# Sheet2.net
KiCad netlist of a schematic drawn in Altium Designer
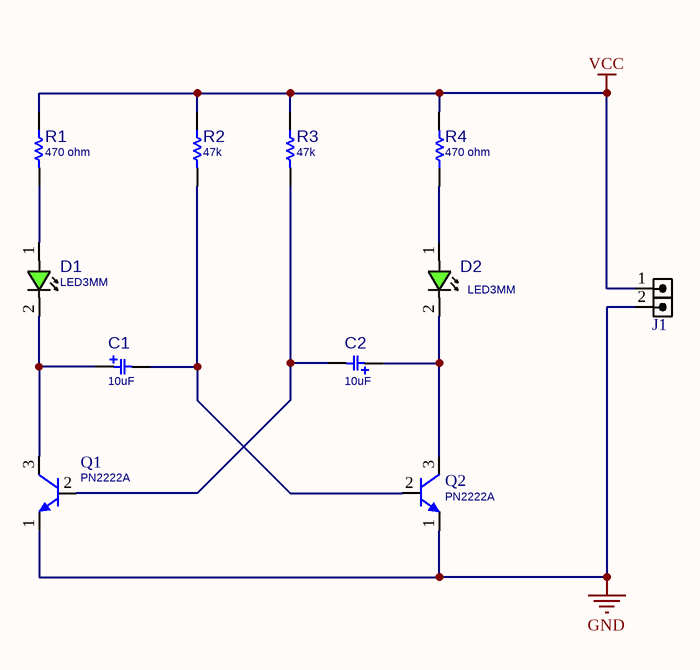
[diagram p0: Sheet2.SchDoc]

(export (version "E")
  (design (tool "Eeschema 10.0.6"))
  (components
    (comp (ref "C1")
      (value "10uF")
      (footprint "C_EL_8X14")
      (description "CAP, THD, ELEC,")
      (fields (field (name "MANF_P#") "MANF_PART#") (field (name "MANF") "MANF"))
      (libsource (lib "passive_thd") (part "CAP_THD_EL"))
    )
    (comp (ref "C2")
      (value "10uF")
      (footprint "C_EL_8X14")
      (description "CAP, THD, ELEC,")
      (fields (field (name "MANF_P#") "MANF_PART#") (field (name "MANF") "MANF"))
      (libsource (lib "passive_thd") (part "CAP_THD_EL"))
    )
    (comp (ref "D1")
      (value "LED3MM")
      (footprint "LED3MM")
      (description "LED, THD, 3MM, GREEN")
      (fields (field (name "MANF") "MANF") (field (name "MANF_P#") "MANF_PART#"))
      (libsource (lib "led(diode)") (part "LED_THD_3MM"))
    )
    (comp (ref "D2")
      (value "LED3MM")
      (footprint "LED3MM")
      (description "LED, THD, 3MM, GREEN")
      (fields (field (name "MANF") "MANF") (field (name "MANF_P#") "MANF_PART#"))
      (libsource (lib "led(diode)") (part "LED_THD_3MM"))
    )
    (comp (ref "J1")
      (value "HDRM2")
      (footprint "HDR_M_1X2")
      (description "CONN, HEADER, Male, pitch: 2.54mm, 2POS")
      (libsource (lib "conn_header_2.54mm_st") (part "HDR_M_1X2"))
    )
    (comp (ref "Q1")
      (value "PN2222A")
      (footprint "TO92_3")
      (description "BJT, NPN, 40v, 0.6A, THD, TO92")
      (fields (field (name "MANF") "DIOTEC"))
      (libsource (lib "transistor_bjt") (part "NPN_PN2222A_TO92"))
    )
    (comp (ref "Q2")
      (value "PN2222A")
      (footprint "TO92_3")
      (description "BJT, NPN, 40v, 0.6A, THD, TO92")
      (fields (field (name "MANF") "DIOTEC"))
      (libsource (lib "transistor_bjt") (part "NPN_PN2222A_TO92"))
    )
    (comp (ref "R1")
      (value "470 ohm")
      (footprint "R025W_AX04")
      (description "RESISTOR, THD")
      (fields (field (name "MANF_P#") "RK73H1ETTP4701F") (field (name "MANF") "KOA SPEER"))
      (libsource (lib "passive_thd") (part "RES_THD"))
    )
    (comp (ref "R2")
      (value "47k")
      (footprint "R025W_AX04")
      (description "RESISTOR, THD")
      (fields (field (name "MANF_P#") "RK73H1ETTP4701F") (field (name "MANF") "KOA SPEER"))
      (libsource (lib "passive_thd") (part "RES_THD"))
    )
    (comp (ref "R3")
      (value "47k")
      (footprint "R025W_AX04")
      (description "RESISTOR, THD")
      (fields (field (name "MANF_P#") "RK73H1ETTP4701F") (field (name "MANF") "KOA SPEER"))
      (libsource (lib "passive_thd") (part "RES_THD"))
    )
    (comp (ref "R4")
      (value "470 ohm")
      (footprint "R025W_AX04")
      (description "RESISTOR, THD")
      (fields (field (name "MANF_P#") "RK73H1ETTP4701F") (field (name "MANF") "KOA SPEER"))
      (libsource (lib "passive_thd") (part "RES_THD"))
    )
  )
  (nets
    (net (code "1") (name "GND") (class "Default")
      (node (ref "J1") (pin "2") (pinfunction "2_2") (pintype "passive"))
      (node (ref "Q1") (pin "1") (pinfunction "E_1") (pintype "passive"))
      (node (ref "Q2") (pin "1") (pinfunction "E_1") (pintype "passive"))
    )
    (net (code "2") (name "Net-(D1-ANODE)") (class "Default")
      (node (ref "D1") (pin "1") (pinfunction "ANODE_1") (pintype "passive"))
      (node (ref "R1") (pin "2") (pinfunction "2_2") (pintype "passive"))
    )
    (net (code "3") (name "Net-(D1-CATHODE)") (class "Default")
      (node (ref "C1") (pin "1") (pinfunction "1_1") (pintype "passive"))
      (node (ref "D1") (pin "2") (pinfunction "CATHODE_2") (pintype "passive"))
      (node (ref "Q1") (pin "3") (pinfunction "C_3") (pintype "passive"))
    )
    (net (code "4") (name "Net-(D2-ANODE)") (class "Default")
      (node (ref "D2") (pin "1") (pinfunction "ANODE_1") (pintype "passive"))
      (node (ref "R4") (pin "1") (pinfunction "1_1") (pintype "passive"))
    )
    (net (code "5") (name "Net-(D2-CATHODE)") (class "Default")
      (node (ref "C2") (pin "1") (pinfunction "1_1") (pintype "passive"))
      (node (ref "D2") (pin "2") (pinfunction "CATHODE_2") (pintype "passive"))
      (node (ref "Q2") (pin "3") (pinfunction "C_3") (pintype "passive"))
    )
    (net (code "6") (name "Net-(Q1-B)") (class "Default")
      (node (ref "C2") (pin "2") (pinfunction "2_2") (pintype "passive"))
      (node (ref "Q1") (pin "2") (pinfunction "B_2") (pintype "passive"))
      (node (ref "R3") (pin "2") (pinfunction "2_2") (pintype "passive"))
    )
    (net (code "7") (name "Net-(Q2-B)") (class "Default")
      (node (ref "C1") (pin "2") (pinfunction "2_2") (pintype "passive"))
      (node (ref "Q2") (pin "2") (pinfunction "B_2") (pintype "passive"))
      (node (ref "R2") (pin "2") (pinfunction "2_2") (pintype "passive"))
    )
    (net (code "8") (name "VCC") (class "Default")
      (node (ref "J1") (pin "1") (pinfunction "1_1") (pintype "passive"))
      (node (ref "R1") (pin "1") (pinfunction "1_1") (pintype "passive"))
      (node (ref "R2") (pin "1") (pinfunction "1_1") (pintype "passive"))
      (node (ref "R3") (pin "1") (pinfunction "1_1") (pintype "passive"))
      (node (ref "R4") (pin "2") (pinfunction "2_2") (pintype "passive"))
    )
  )
)
